# control_pcb_rev1-1.net
KiCad netlist of a schematic drawn in EAGLE
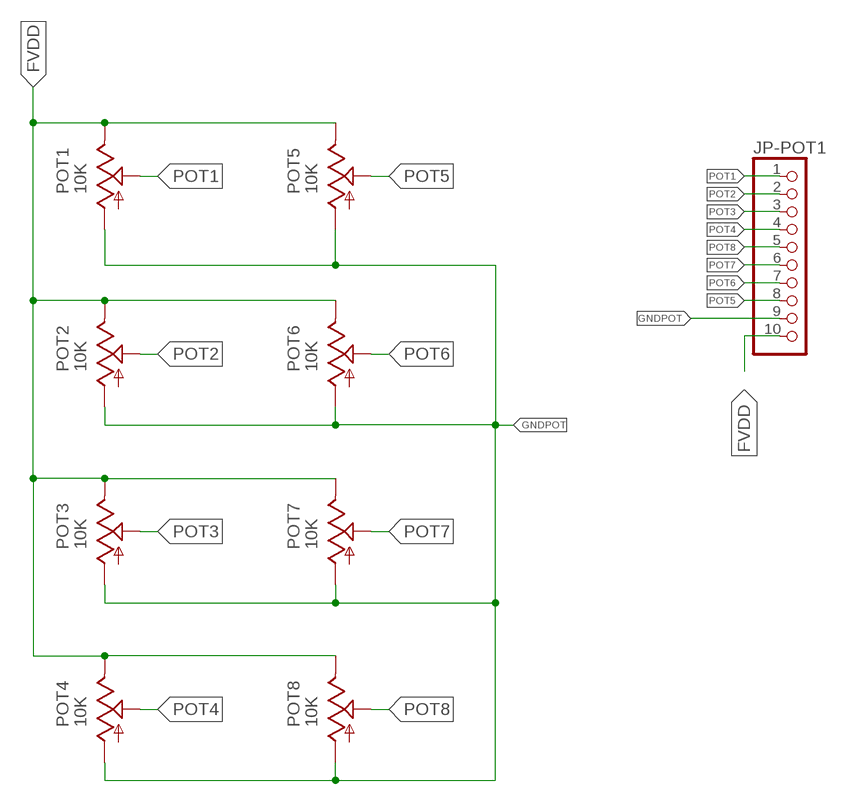
[diagram p0: schematic, sheet 1]
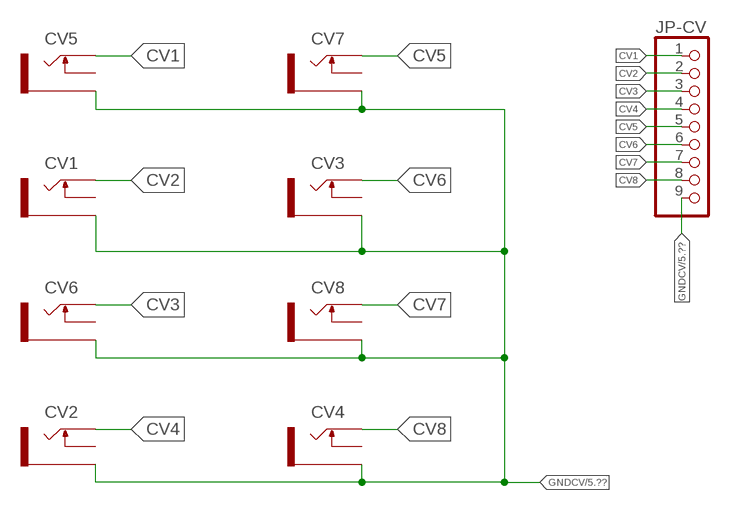
[diagram p1: schematic, sheet 2]
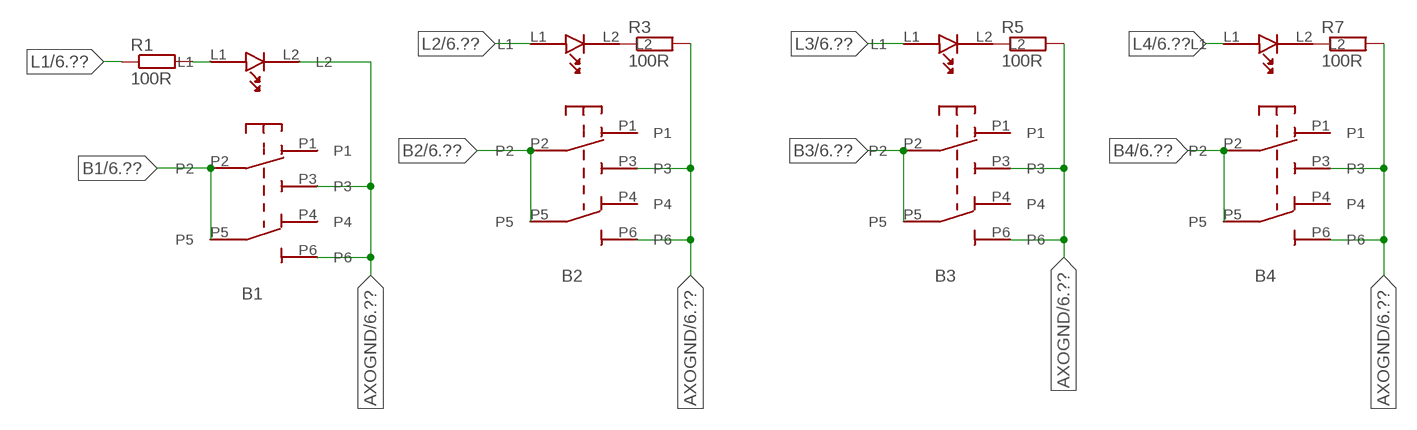
[diagram p2: schematic, sheet 3]
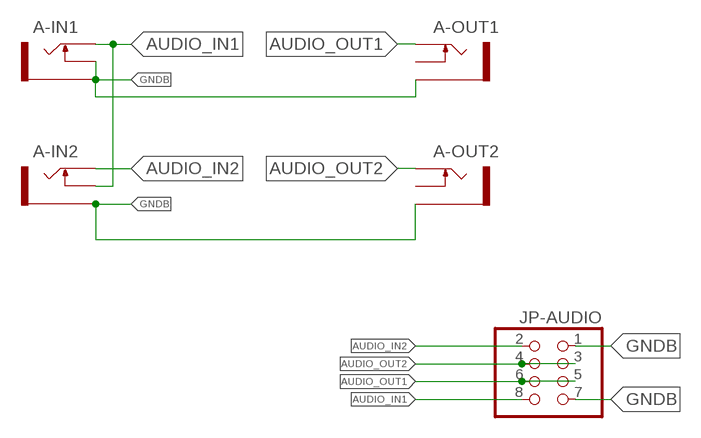
[diagram p3: schematic, sheet 4]
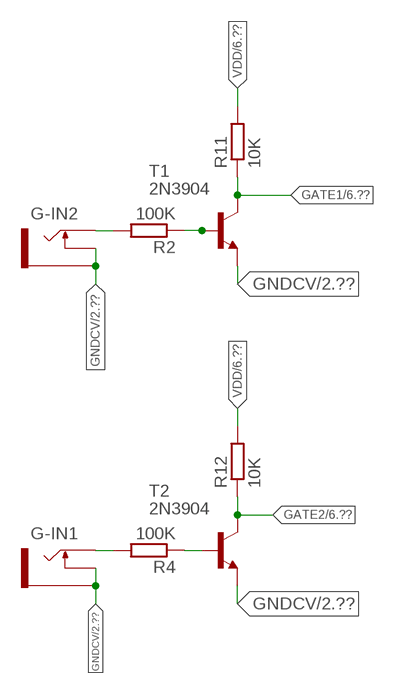
[diagram p4: schematic, sheet 5]
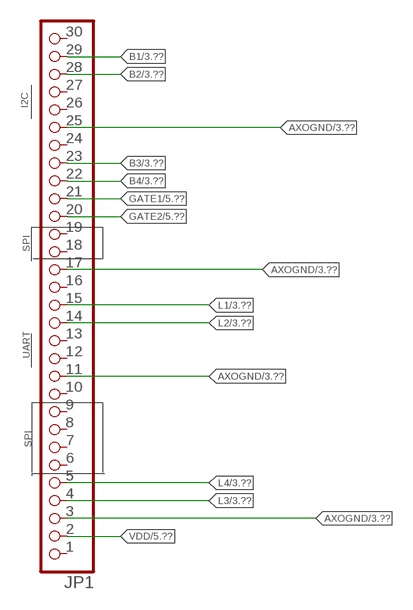
[diagram p5: schematic, sheet 6]

(export (version "E")
  (design (tool "Eeschema 10.0.6"))
  (components
    (comp (ref "CV1")
      (value "THONKICONNNEW")
      (footprint "eagle-import:WQP-PJ301M-12_JACK")
      (libsource (lib "eagle-import") (part "THONKICONNNEW"))
    )
    (comp (ref "CV2")
      (value "THONKICONNNEW")
      (footprint "eagle-import:WQP-PJ301M-12_JACK")
      (libsource (lib "eagle-import") (part "THONKICONNNEW"))
    )
    (comp (ref "CV3")
      (value "THONKICONNNEW")
      (footprint "eagle-import:WQP-PJ301M-12_JACK")
      (libsource (lib "eagle-import") (part "THONKICONNNEW"))
    )
    (comp (ref "CV4")
      (value "THONKICONNNEW")
      (footprint "eagle-import:WQP-PJ301M-12_JACK")
      (libsource (lib "eagle-import") (part "THONKICONNNEW"))
    )
    (comp (ref "CV5")
      (value "THONKICONNNEW")
      (footprint "eagle-import:WQP-PJ301M-12_JACK")
      (libsource (lib "eagle-import") (part "THONKICONNNEW"))
    )
    (comp (ref "CV6")
      (value "THONKICONNNEW")
      (footprint "eagle-import:WQP-PJ301M-12_JACK")
      (libsource (lib "eagle-import") (part "THONKICONNNEW"))
    )
    (comp (ref "CV7")
      (value "THONKICONNNEW")
      (footprint "eagle-import:WQP-PJ301M-12_JACK")
      (libsource (lib "eagle-import") (part "THONKICONNNEW"))
    )
    (comp (ref "CV8")
      (value "THONKICONNNEW")
      (footprint "eagle-import:WQP-PJ301M-12_JACK")
      (libsource (lib "eagle-import") (part "THONKICONNNEW"))
    )
    (comp (ref "JP-CV")
      (value "PINHD-1X9_2.54")
      (footprint "eagle-import:1X09")
      (libsource (lib "eagle-import") (part "PINHD-1X9_2.54"))
    )
    (comp (ref "G-IN1")
      (value "THONKICONNNEW")
      (footprint "eagle-import:WQP-PJ301M-12_JACK")
      (libsource (lib "eagle-import") (part "THONKICONNNEW"))
    )
    (comp (ref "G-IN2")
      (value "THONKICONNNEW")
      (footprint "eagle-import:WQP-PJ301M-12_JACK")
      (libsource (lib "eagle-import") (part "THONKICONNNEW"))
    )
    (comp (ref "R2")
      (value "100K")
      (footprint "eagle-import:0207_7")
      (libsource (lib "eagle-import") (part "R-EU_0207/7"))
    )
    (comp (ref "R4")
      (value "100K")
      (footprint "eagle-import:0207_7")
      (libsource (lib "eagle-import") (part "R-EU_0207/7"))
    )
    (comp (ref "R11")
      (value "10K")
      (footprint "eagle-import:0207_7")
      (libsource (lib "eagle-import") (part "R-EU_0207/7"))
    )
    (comp (ref "R12")
      (value "10K")
      (footprint "eagle-import:0207_7")
      (libsource (lib "eagle-import") (part "R-EU_0207/7"))
    )
    (comp (ref "T1")
      (value "2N3904")
      (footprint "eagle-import:TO92")
      (libsource (lib "eagle-import") (part "2N3904"))
    )
    (comp (ref "T2")
      (value "2N3904")
      (footprint "eagle-import:TO92")
      (libsource (lib "eagle-import") (part "2N3904"))
    )
    (comp (ref "JP-POT1")
      (value "PINHD-1X10_2.54")
      (footprint "eagle-import:1X10")
      (libsource (lib "eagle-import") (part "PINHD-1X10_2.54"))
    )
    (comp (ref "POT1")
      (value "10K")
      (footprint "eagle-import:9MM_SNAP-IN_POT")
      (libsource (lib "eagle-import") (part "9MM_SNAP-IN_POT_"))
    )
    (comp (ref "POT2")
      (value "10K")
      (footprint "eagle-import:9MM_SNAP-IN_POT")
      (libsource (lib "eagle-import") (part "9MM_SNAP-IN_POT_"))
    )
    (comp (ref "POT3")
      (value "10K")
      (footprint "eagle-import:9MM_SNAP-IN_POT")
      (libsource (lib "eagle-import") (part "9MM_SNAP-IN_POT_"))
    )
    (comp (ref "POT4")
      (value "10K")
      (footprint "eagle-import:9MM_SNAP-IN_POT")
      (libsource (lib "eagle-import") (part "9MM_SNAP-IN_POT_"))
    )
    (comp (ref "POT5")
      (value "10K")
      (footprint "eagle-import:9MM_SNAP-IN_POT")
      (libsource (lib "eagle-import") (part "9MM_SNAP-IN_POT_"))
    )
    (comp (ref "POT6")
      (value "10K")
      (footprint "eagle-import:9MM_SNAP-IN_POT")
      (libsource (lib "eagle-import") (part "9MM_SNAP-IN_POT_"))
    )
    (comp (ref "POT7")
      (value "10K")
      (footprint "eagle-import:9MM_SNAP-IN_POT")
      (libsource (lib "eagle-import") (part "9MM_SNAP-IN_POT_"))
    )
    (comp (ref "POT8")
      (value "10K")
      (footprint "eagle-import:9MM_SNAP-IN_POT")
      (libsource (lib "eagle-import") (part "9MM_SNAP-IN_POT_"))
    )
    (comp (ref "A-IN1")
      (value "THONKICONNNEW")
      (footprint "eagle-import:WQP-PJ301M-12_JACK")
      (libsource (lib "eagle-import") (part "THONKICONNNEW"))
    )
    (comp (ref "A-IN2")
      (value "THONKICONNNEW")
      (footprint "eagle-import:WQP-PJ301M-12_JACK")
      (libsource (lib "eagle-import") (part "THONKICONNNEW"))
    )
    (comp (ref "A-OUT1")
      (value "THONKICONNNEW")
      (footprint "eagle-import:WQP-PJ301M-12_JACK")
      (libsource (lib "eagle-import") (part "THONKICONNNEW"))
    )
    (comp (ref "A-OUT2")
      (value "THONKICONNNEW")
      (footprint "eagle-import:WQP-PJ301M-12_JACK")
      (libsource (lib "eagle-import") (part "THONKICONNNEW"))
    )
    (comp (ref "JP-AUDIO")
      (value "PINHD-2X4_2.54")
      (footprint "eagle-import:2X04")
      (libsource (lib "eagle-import") (part "PINHD-2X4_2.54"))
    )
    (comp (ref "B1")
      (value "LP4OA1PBCTG/D6")
      (footprint "eagle-import:LP4OA1PBCT")
      (libsource (lib "eagle-import") (part "LP4OA1PBCTG"))
    )
    (comp (ref "B2")
      (value "LP4OA1PBCTG/D6")
      (footprint "eagle-import:LP4OA1PBCT")
      (libsource (lib "eagle-import") (part "LP4OA1PBCTG"))
    )
    (comp (ref "B3")
      (value "LP4OA1PBCTG/D6")
      (footprint "eagle-import:LP4OA1PBCT")
      (libsource (lib "eagle-import") (part "LP4OA1PBCTG"))
    )
    (comp (ref "B4")
      (value "LP4OA1PBCTG/D6")
      (footprint "eagle-import:LP4OA1PBCT")
      (libsource (lib "eagle-import") (part "LP4OA1PBCTG"))
    )
    (comp (ref "R1")
      (value "100R")
      (footprint "eagle-import:0207_7")
      (libsource (lib "eagle-import") (part "R-EU_0207/7"))
    )
    (comp (ref "R3")
      (value "100R")
      (footprint "eagle-import:0207_7")
      (libsource (lib "eagle-import") (part "R-EU_0207/7"))
    )
    (comp (ref "R5")
      (value "100R")
      (footprint "eagle-import:0207_7")
      (libsource (lib "eagle-import") (part "R-EU_0207/7"))
    )
    (comp (ref "R7")
      (value "100R")
      (footprint "eagle-import:0207_7")
      (libsource (lib "eagle-import") (part "R-EU_0207/7"))
    )
    (comp (ref "JP1")
      (value "PINHD-1X30")
      (footprint "eagle-import:1X30")
      (libsource (lib "eagle-import") (part "PINHD-1X30"))
    )
  )
  (nets
    (net (code "1") (name "AUDIO_IN1") (class "Default")
      (node (ref "A-IN1") (pin "P$1_TIP") (pinfunction "TIP_P$1_TIP") (pintype "passive"))
      (node (ref "A-IN2") (pin "P$2_SWITCH") (pinfunction "SWITCH_P$2_SWITCH") (pintype "passive"))
      (node (ref "JP-AUDIO") (pin "8") (pinfunction "8_8") (pintype "passive"))
    )
    (net (code "2") (name "AUDIO_IN2") (class "Default")
      (node (ref "A-IN2") (pin "P$1_TIP") (pinfunction "TIP_P$1_TIP") (pintype "passive"))
      (node (ref "JP-AUDIO") (pin "2") (pinfunction "2_2") (pintype "passive"))
    )
    (net (code "3") (name "AUDIO_OUT1") (class "Default")
      (node (ref "A-OUT1") (pin "P$1_TIP") (pinfunction "TIP_P$1_TIP") (pintype "passive"))
      (node (ref "JP-AUDIO") (pin "5") (pinfunction "5_5") (pintype "passive"))
      (node (ref "JP-AUDIO") (pin "6") (pinfunction "6_6") (pintype "passive"))
    )
    (net (code "4") (name "AUDIO_OUT2") (class "Default")
      (node (ref "A-OUT2") (pin "P$1_TIP") (pinfunction "TIP_P$1_TIP") (pintype "passive"))
      (node (ref "JP-AUDIO") (pin "3") (pinfunction "3_3") (pintype "passive"))
      (node (ref "JP-AUDIO") (pin "4") (pinfunction "4_4") (pintype "passive"))
    )
    (net (code "5") (name "AXOGND") (class "Default")
      (node (ref "B1") (pin "L2") (pinfunction "L2_L2") (pintype "output"))
      (node (ref "B1") (pin "P3") (pinfunction "P3_P3") (pintype "bidirectional"))
      (node (ref "B1") (pin "P6") (pinfunction "P6_P6") (pintype "bidirectional"))
      (node (ref "B2") (pin "P3") (pinfunction "P3_P3") (pintype "bidirectional"))
      (node (ref "B2") (pin "P6") (pinfunction "P6_P6") (pintype "bidirectional"))
      (node (ref "B3") (pin "P3") (pinfunction "P3_P3") (pintype "bidirectional"))
      (node (ref "B3") (pin "P6") (pinfunction "P6_P6") (pintype "bidirectional"))
      (node (ref "B4") (pin "P3") (pinfunction "P3_P3") (pintype "bidirectional"))
      (node (ref "B4") (pin "P6") (pinfunction "P6_P6") (pintype "bidirectional"))
      (node (ref "JP1") (pin "11") (pinfunction "11_11") (pintype "passive"))
      (node (ref "JP1") (pin "17") (pinfunction "17_17") (pintype "passive"))
      (node (ref "JP1") (pin "25") (pinfunction "25_25") (pintype "passive"))
      (node (ref "JP1") (pin "3") (pinfunction "3_3") (pintype "passive"))
      (node (ref "R3") (pin "2") (pinfunction "2_2") (pintype "passive"))
      (node (ref "R5") (pin "2") (pinfunction "2_2") (pintype "passive"))
      (node (ref "R7") (pin "2") (pinfunction "2_2") (pintype "passive"))
    )
    (net (code "6") (name "B1") (class "Default")
      (node (ref "B1") (pin "P2") (pinfunction "P2_P2") (pintype "bidirectional"))
      (node (ref "B1") (pin "P5") (pinfunction "P5_P5") (pintype "bidirectional"))
      (node (ref "JP1") (pin "29") (pinfunction "29_29") (pintype "passive"))
    )
    (net (code "7") (name "B2") (class "Default")
      (node (ref "B2") (pin "P2") (pinfunction "P2_P2") (pintype "bidirectional"))
      (node (ref "B2") (pin "P5") (pinfunction "P5_P5") (pintype "bidirectional"))
      (node (ref "JP1") (pin "28") (pinfunction "28_28") (pintype "passive"))
    )
    (net (code "8") (name "B3") (class "Default")
      (node (ref "B3") (pin "P2") (pinfunction "P2_P2") (pintype "bidirectional"))
      (node (ref "B3") (pin "P5") (pinfunction "P5_P5") (pintype "bidirectional"))
      (node (ref "JP1") (pin "23") (pinfunction "23_23") (pintype "passive"))
    )
    (net (code "9") (name "B4") (class "Default")
      (node (ref "B4") (pin "P2") (pinfunction "P2_P2") (pintype "bidirectional"))
      (node (ref "B4") (pin "P5") (pinfunction "P5_P5") (pintype "bidirectional"))
      (node (ref "JP1") (pin "22") (pinfunction "22_22") (pintype "passive"))
    )
    (net (code "10") (name "CV1") (class "Default")
      (node (ref "CV5") (pin "P$1_TIP") (pinfunction "TIP_P$1_TIP") (pintype "passive"))
      (node (ref "JP-CV") (pin "1") (pinfunction "1_1") (pintype "passive"))
    )
    (net (code "11") (name "CV2") (class "Default")
      (node (ref "CV1") (pin "P$1_TIP") (pinfunction "TIP_P$1_TIP") (pintype "passive"))
      (node (ref "JP-CV") (pin "2") (pinfunction "2_2") (pintype "passive"))
    )
    (net (code "12") (name "CV3") (class "Default")
      (node (ref "CV6") (pin "P$1_TIP") (pinfunction "TIP_P$1_TIP") (pintype "passive"))
      (node (ref "JP-CV") (pin "3") (pinfunction "3_3") (pintype "passive"))
    )
    (net (code "13") (name "CV4") (class "Default")
      (node (ref "CV2") (pin "P$1_TIP") (pinfunction "TIP_P$1_TIP") (pintype "passive"))
      (node (ref "JP-CV") (pin "4") (pinfunction "4_4") (pintype "passive"))
    )
    (net (code "14") (name "CV5") (class "Default")
      (node (ref "CV7") (pin "P$1_TIP") (pinfunction "TIP_P$1_TIP") (pintype "passive"))
      (node (ref "JP-CV") (pin "5") (pinfunction "5_5") (pintype "passive"))
    )
    (net (code "15") (name "CV6") (class "Default")
      (node (ref "CV3") (pin "P$1_TIP") (pinfunction "TIP_P$1_TIP") (pintype "passive"))
      (node (ref "JP-CV") (pin "6") (pinfunction "6_6") (pintype "passive"))
    )
    (net (code "16") (name "CV7") (class "Default")
      (node (ref "CV8") (pin "P$1_TIP") (pinfunction "TIP_P$1_TIP") (pintype "passive"))
      (node (ref "JP-CV") (pin "7") (pinfunction "7_7") (pintype "passive"))
    )
    (net (code "17") (name "CV8") (class "Default")
      (node (ref "CV4") (pin "P$1_TIP") (pinfunction "TIP_P$1_TIP") (pintype "passive"))
      (node (ref "JP-CV") (pin "8") (pinfunction "8_8") (pintype "passive"))
    )
    (net (code "18") (name "FVDD") (class "Default")
      (node (ref "JP-POT1") (pin "10") (pinfunction "10_10") (pintype "passive"))
      (node (ref "POT1") (pin "3") (pinfunction "E_3") (pintype "passive"))
      (node (ref "POT2") (pin "3") (pinfunction "E_3") (pintype "passive"))
      (node (ref "POT3") (pin "3") (pinfunction "E_3") (pintype "passive"))
      (node (ref "POT4") (pin "3") (pinfunction "E_3") (pintype "passive"))
      (node (ref "POT5") (pin "3") (pinfunction "E_3") (pintype "passive"))
      (node (ref "POT6") (pin "3") (pinfunction "E_3") (pintype "passive"))
      (node (ref "POT7") (pin "3") (pinfunction "E_3") (pintype "passive"))
      (node (ref "POT8") (pin "3") (pinfunction "E_3") (pintype "passive"))
    )
    (net (code "19") (name "GATE1") (class "Default")
      (node (ref "JP1") (pin "21") (pinfunction "21_21") (pintype "passive"))
      (node (ref "R11") (pin "1") (pinfunction "1_1") (pintype "passive"))
      (node (ref "T1") (pin "1") (pinfunction "C_1") (pintype "passive"))
    )
    (net (code "20") (name "GATE2") (class "Default")
      (node (ref "JP1") (pin "20") (pinfunction "20_20") (pintype "passive"))
      (node (ref "R12") (pin "1") (pinfunction "1_1") (pintype "passive"))
      (node (ref "T2") (pin "1") (pinfunction "C_1") (pintype "passive"))
    )
    (net (code "21") (name "GNDB") (class "Default")
      (node (ref "A-IN1") (pin "P$2_SWITCH") (pinfunction "SWITCH_P$2_SWITCH") (pintype "passive"))
      (node (ref "A-IN1") (pin "P$3_SLEEVE") (pinfunction "SLEEVE_P$3_SLEEVE") (pintype "passive"))
      (node (ref "A-IN2") (pin "P$3_SLEEVE") (pinfunction "SLEEVE_P$3_SLEEVE") (pintype "passive"))
      (node (ref "A-OUT1") (pin "P$3_SLEEVE") (pinfunction "SLEEVE_P$3_SLEEVE") (pintype "passive"))
      (node (ref "A-OUT2") (pin "P$3_SLEEVE") (pinfunction "SLEEVE_P$3_SLEEVE") (pintype "passive"))
      (node (ref "JP-AUDIO") (pin "1") (pinfunction "1_1") (pintype "passive"))
      (node (ref "JP-AUDIO") (pin "7") (pinfunction "7_7") (pintype "passive"))
    )
    (net (code "22") (name "GNDCV") (class "Default")
      (node (ref "CV1") (pin "P$3_SLEEVE") (pinfunction "SLEEVE_P$3_SLEEVE") (pintype "passive"))
      (node (ref "CV2") (pin "P$3_SLEEVE") (pinfunction "SLEEVE_P$3_SLEEVE") (pintype "passive"))
      (node (ref "CV3") (pin "P$3_SLEEVE") (pinfunction "SLEEVE_P$3_SLEEVE") (pintype "passive"))
      (node (ref "CV4") (pin "P$3_SLEEVE") (pinfunction "SLEEVE_P$3_SLEEVE") (pintype "passive"))
      (node (ref "CV5") (pin "P$3_SLEEVE") (pinfunction "SLEEVE_P$3_SLEEVE") (pintype "passive"))
      (node (ref "CV6") (pin "P$3_SLEEVE") (pinfunction "SLEEVE_P$3_SLEEVE") (pintype "passive"))
      (node (ref "CV7") (pin "P$3_SLEEVE") (pinfunction "SLEEVE_P$3_SLEEVE") (pintype "passive"))
      (node (ref "CV8") (pin "P$3_SLEEVE") (pinfunction "SLEEVE_P$3_SLEEVE") (pintype "passive"))
      (node (ref "G-IN1") (pin "P$2_SWITCH") (pinfunction "SWITCH_P$2_SWITCH") (pintype "passive"))
      (node (ref "G-IN1") (pin "P$3_SLEEVE") (pinfunction "SLEEVE_P$3_SLEEVE") (pintype "passive"))
      (node (ref "G-IN2") (pin "P$2_SWITCH") (pinfunction "SWITCH_P$2_SWITCH") (pintype "passive"))
      (node (ref "G-IN2") (pin "P$3_SLEEVE") (pinfunction "SLEEVE_P$3_SLEEVE") (pintype "passive"))
      (node (ref "JP-CV") (pin "9") (pinfunction "9_9") (pintype "passive"))
      (node (ref "T1") (pin "3") (pinfunction "E_3") (pintype "passive"))
      (node (ref "T2") (pin "3") (pinfunction "E_3") (pintype "passive"))
    )
    (net (code "23") (name "GNDPOT") (class "Default")
      (node (ref "JP-POT1") (pin "9") (pinfunction "9_9") (pintype "passive"))
      (node (ref "POT1") (pin "1") (pinfunction "A_1") (pintype "passive"))
      (node (ref "POT2") (pin "1") (pinfunction "A_1") (pintype "passive"))
      (node (ref "POT3") (pin "1") (pinfunction "A_1") (pintype "passive"))
      (node (ref "POT4") (pin "1") (pinfunction "A_1") (pintype "passive"))
      (node (ref "POT5") (pin "1") (pinfunction "A_1") (pintype "passive"))
      (node (ref "POT6") (pin "1") (pinfunction "A_1") (pintype "passive"))
      (node (ref "POT7") (pin "1") (pinfunction "A_1") (pintype "passive"))
      (node (ref "POT8") (pin "1") (pinfunction "A_1") (pintype "passive"))
    )
    (net (code "24") (name "L1") (class "Default")
      (node (ref "JP1") (pin "15") (pinfunction "15_15") (pintype "passive"))
      (node (ref "R1") (pin "1") (pinfunction "1_1") (pintype "passive"))
    )
    (net (code "25") (name "L2") (class "Default")
      (node (ref "B2") (pin "L1") (pinfunction "L1_L1") (pintype "input"))
      (node (ref "JP1") (pin "14") (pinfunction "14_14") (pintype "passive"))
    )
    (net (code "26") (name "L3") (class "Default")
      (node (ref "B3") (pin "L1") (pinfunction "L1_L1") (pintype "input"))
      (node (ref "JP1") (pin "4") (pinfunction "4_4") (pintype "passive"))
    )
    (net (code "27") (name "L4") (class "Default")
      (node (ref "B4") (pin "L1") (pinfunction "L1_L1") (pintype "input"))
      (node (ref "JP1") (pin "5") (pinfunction "5_5") (pintype "passive"))
    )
    (net (code "28") (name "Net-(B1-PadL1)") (class "Default")
      (node (ref "B1") (pin "L1") (pinfunction "L1_L1") (pintype "input"))
      (node (ref "R1") (pin "2") (pinfunction "2_2") (pintype "passive"))
    )
    (net (code "29") (name "Net-(B2-PadL2)") (class "Default")
      (node (ref "B2") (pin "L2") (pinfunction "L2_L2") (pintype "output"))
      (node (ref "R3") (pin "1") (pinfunction "1_1") (pintype "passive"))
    )
    (net (code "30") (name "Net-(B3-PadL2)") (class "Default")
      (node (ref "B3") (pin "L2") (pinfunction "L2_L2") (pintype "output"))
      (node (ref "R5") (pin "1") (pinfunction "1_1") (pintype "passive"))
    )
    (net (code "31") (name "Net-(B4-PadL2)") (class "Default")
      (node (ref "B4") (pin "L2") (pinfunction "L2_L2") (pintype "output"))
      (node (ref "R7") (pin "1") (pinfunction "1_1") (pintype "passive"))
    )
    (net (code "32") (name "Net-(G-IN1-TIP)") (class "Default")
      (node (ref "G-IN1") (pin "P$1_TIP") (pinfunction "TIP_P$1_TIP") (pintype "passive"))
      (node (ref "R4") (pin "2") (pinfunction "2_2") (pintype "passive"))
    )
    (net (code "33") (name "Net-(G-IN2-TIP)") (class "Default")
      (node (ref "G-IN2") (pin "P$1_TIP") (pinfunction "TIP_P$1_TIP") (pintype "passive"))
      (node (ref "R2") (pin "2") (pinfunction "2_2") (pintype "passive"))
    )
    (net (code "34") (name "Net-(T1-B)") (class "Default")
      (node (ref "R2") (pin "1") (pinfunction "1_1") (pintype "passive"))
      (node (ref "T1") (pin "2") (pinfunction "B_2") (pintype "passive"))
    )
    (net (code "35") (name "Net-(T2-B)") (class "Default")
      (node (ref "R4") (pin "1") (pinfunction "1_1") (pintype "passive"))
      (node (ref "T2") (pin "2") (pinfunction "B_2") (pintype "passive"))
    )
    (net (code "36") (name "POT1") (class "Default")
      (node (ref "JP-POT1") (pin "1") (pinfunction "1_1") (pintype "passive"))
      (node (ref "POT1") (pin "2") (pinfunction "S_2") (pintype "passive"))
    )
    (net (code "37") (name "POT2") (class "Default")
      (node (ref "JP-POT1") (pin "2") (pinfunction "2_2") (pintype "passive"))
      (node (ref "POT2") (pin "2") (pinfunction "S_2") (pintype "passive"))
    )
    (net (code "38") (name "POT3") (class "Default")
      (node (ref "JP-POT1") (pin "3") (pinfunction "3_3") (pintype "passive"))
      (node (ref "POT3") (pin "2") (pinfunction "S_2") (pintype "passive"))
    )
    (net (code "39") (name "POT4") (class "Default")
      (node (ref "JP-POT1") (pin "4") (pinfunction "4_4") (pintype "passive"))
      (node (ref "POT4") (pin "2") (pinfunction "S_2") (pintype "passive"))
    )
    (net (code "40") (name "POT5") (class "Default")
      (node (ref "JP-POT1") (pin "8") (pinfunction "8_8") (pintype "passive"))
      (node (ref "POT5") (pin "2") (pinfunction "S_2") (pintype "passive"))
    )
    (net (code "41") (name "POT6") (class "Default")
      (node (ref "JP-POT1") (pin "7") (pinfunction "7_7") (pintype "passive"))
      (node (ref "POT6") (pin "2") (pinfunction "S_2") (pintype "passive"))
    )
    (net (code "42") (name "POT7") (class "Default")
      (node (ref "JP-POT1") (pin "6") (pinfunction "6_6") (pintype "passive"))
      (node (ref "POT7") (pin "2") (pinfunction "S_2") (pintype "passive"))
    )
    (net (code "43") (name "POT8") (class "Default")
      (node (ref "JP-POT1") (pin "5") (pinfunction "5_5") (pintype "passive"))
      (node (ref "POT8") (pin "2") (pinfunction "S_2") (pintype "passive"))
    )
    (net (code "44") (name "VDD") (class "Default")
      (node (ref "JP1") (pin "2") (pinfunction "2_2") (pintype "passive"))
      (node (ref "R11") (pin "2") (pinfunction "2_2") (pintype "passive"))
      (node (ref "R12") (pin "2") (pinfunction "2_2") (pintype "passive"))
    )
    (net (code "45") (name "unconnected-(A-OUT1-SWITCH-PadP$2_SWITCH)") (class "Default")
      (node (ref "A-OUT1") (pin "P$2_SWITCH") (pinfunction "SWITCH_P$2_SWITCH") (pintype "passive"))
    )
    (net (code "46") (name "unconnected-(A-OUT2-SWITCH-PadP$2_SWITCH)") (class "Default")
      (node (ref "A-OUT2") (pin "P$2_SWITCH") (pinfunction "SWITCH_P$2_SWITCH") (pintype "passive"))
    )
    (net (code "47") (name "unconnected-(B1-PadP1)") (class "Default")
      (node (ref "B1") (pin "P1") (pinfunction "P1_P1") (pintype "bidirectional"))
    )
    (net (code "48") (name "unconnected-(B1-PadP4)") (class "Default")
      (node (ref "B1") (pin "P4") (pinfunction "P4_P4") (pintype "bidirectional"))
    )
    (net (code "49") (name "unconnected-(B2-PadP1)") (class "Default")
      (node (ref "B2") (pin "P1") (pinfunction "P1_P1") (pintype "bidirectional"))
    )
    (net (code "50") (name "unconnected-(B2-PadP4)") (class "Default")
      (node (ref "B2") (pin "P4") (pinfunction "P4_P4") (pintype "bidirectional"))
    )
    (net (code "51") (name "unconnected-(B3-PadP1)") (class "Default")
      (node (ref "B3") (pin "P1") (pinfunction "P1_P1") (pintype "bidirectional"))
    )
    (net (code "52") (name "unconnected-(B3-PadP4)") (class "Default")
      (node (ref "B3") (pin "P4") (pinfunction "P4_P4") (pintype "bidirectional"))
    )
    (net (code "53") (name "unconnected-(B4-PadP1)") (class "Default")
      (node (ref "B4") (pin "P1") (pinfunction "P1_P1") (pintype "bidirectional"))
    )
    (net (code "54") (name "unconnected-(B4-PadP4)") (class "Default")
      (node (ref "B4") (pin "P4") (pinfunction "P4_P4") (pintype "bidirectional"))
    )
    (net (code "55") (name "unconnected-(CV1-SWITCH-PadP$2_SWITCH)") (class "Default")
      (node (ref "CV1") (pin "P$2_SWITCH") (pinfunction "SWITCH_P$2_SWITCH") (pintype "passive"))
    )
    (net (code "56") (name "unconnected-(CV2-SWITCH-PadP$2_SWITCH)") (class "Default")
      (node (ref "CV2") (pin "P$2_SWITCH") (pinfunction "SWITCH_P$2_SWITCH") (pintype "passive"))
    )
    (net (code "57") (name "unconnected-(CV3-SWITCH-PadP$2_SWITCH)") (class "Default")
      (node (ref "CV3") (pin "P$2_SWITCH") (pinfunction "SWITCH_P$2_SWITCH") (pintype "passive"))
    )
    (net (code "58") (name "unconnected-(CV4-SWITCH-PadP$2_SWITCH)") (class "Default")
      (node (ref "CV4") (pin "P$2_SWITCH") (pinfunction "SWITCH_P$2_SWITCH") (pintype "passive"))
    )
    (net (code "59") (name "unconnected-(CV5-SWITCH-PadP$2_SWITCH)") (class "Default")
      (node (ref "CV5") (pin "P$2_SWITCH") (pinfunction "SWITCH_P$2_SWITCH") (pintype "passive"))
    )
    (net (code "60") (name "unconnected-(CV6-SWITCH-PadP$2_SWITCH)") (class "Default")
      (node (ref "CV6") (pin "P$2_SWITCH") (pinfunction "SWITCH_P$2_SWITCH") (pintype "passive"))
    )
    (net (code "61") (name "unconnected-(CV7-SWITCH-PadP$2_SWITCH)") (class "Default")
      (node (ref "CV7") (pin "P$2_SWITCH") (pinfunction "SWITCH_P$2_SWITCH") (pintype "passive"))
    )
    (net (code "62") (name "unconnected-(CV8-SWITCH-PadP$2_SWITCH)") (class "Default")
      (node (ref "CV8") (pin "P$2_SWITCH") (pinfunction "SWITCH_P$2_SWITCH") (pintype "passive"))
    )
    (net (code "63") (name "unconnected-(JP1-Pad1)") (class "Default")
      (node (ref "JP1") (pin "1") (pinfunction "1_1") (pintype "passive"))
    )
    (net (code "64") (name "unconnected-(JP1-Pad6)") (class "Default")
      (node (ref "JP1") (pin "6") (pinfunction "6_6") (pintype "passive"))
    )
    (net (code "65") (name "unconnected-(JP1-Pad7)") (class "Default")
      (node (ref "JP1") (pin "7") (pinfunction "7_7") (pintype "passive"))
    )
    (net (code "66") (name "unconnected-(JP1-Pad8)") (class "Default")
      (node (ref "JP1") (pin "8") (pinfunction "8_8") (pintype "passive"))
    )
    (net (code "67") (name "unconnected-(JP1-Pad9)") (class "Default")
      (node (ref "JP1") (pin "9") (pinfunction "9_9") (pintype "passive"))
    )
    (net (code "68") (name "unconnected-(JP1-Pad10)") (class "Default")
      (node (ref "JP1") (pin "10") (pinfunction "10_10") (pintype "passive"))
    )
    (net (code "69") (name "unconnected-(JP1-Pad12)") (class "Default")
      (node (ref "JP1") (pin "12") (pinfunction "12_12") (pintype "passive"))
    )
    (net (code "70") (name "unconnected-(JP1-Pad13)") (class "Default")
      (node (ref "JP1") (pin "13") (pinfunction "13_13") (pintype "passive"))
    )
    (net (code "71") (name "unconnected-(JP1-Pad16)") (class "Default")
      (node (ref "JP1") (pin "16") (pinfunction "16_16") (pintype "passive"))
    )
    (net (code "72") (name "unconnected-(JP1-Pad18)") (class "Default")
      (node (ref "JP1") (pin "18") (pinfunction "18_18") (pintype "passive"))
    )
    (net (code "73") (name "unconnected-(JP1-Pad19)") (class "Default")
      (node (ref "JP1") (pin "19") (pinfunction "19_19") (pintype "passive"))
    )
    (net (code "74") (name "unconnected-(JP1-Pad24)") (class "Default")
      (node (ref "JP1") (pin "24") (pinfunction "24_24") (pintype "passive"))
    )
    (net (code "75") (name "unconnected-(JP1-Pad26)") (class "Default")
      (node (ref "JP1") (pin "26") (pinfunction "26_26") (pintype "passive"))
    )
    (net (code "76") (name "unconnected-(JP1-Pad27)") (class "Default")
      (node (ref "JP1") (pin "27") (pinfunction "27_27") (pintype "passive"))
    )
    (net (code "77") (name "unconnected-(JP1-Pad30)") (class "Default")
      (node (ref "JP1") (pin "30") (pinfunction "30_30") (pintype "passive"))
    )
  )
)
